# Adafruit_Qualia_S3_RGB666.net
KiCad netlist of a schematic drawn in EAGLE
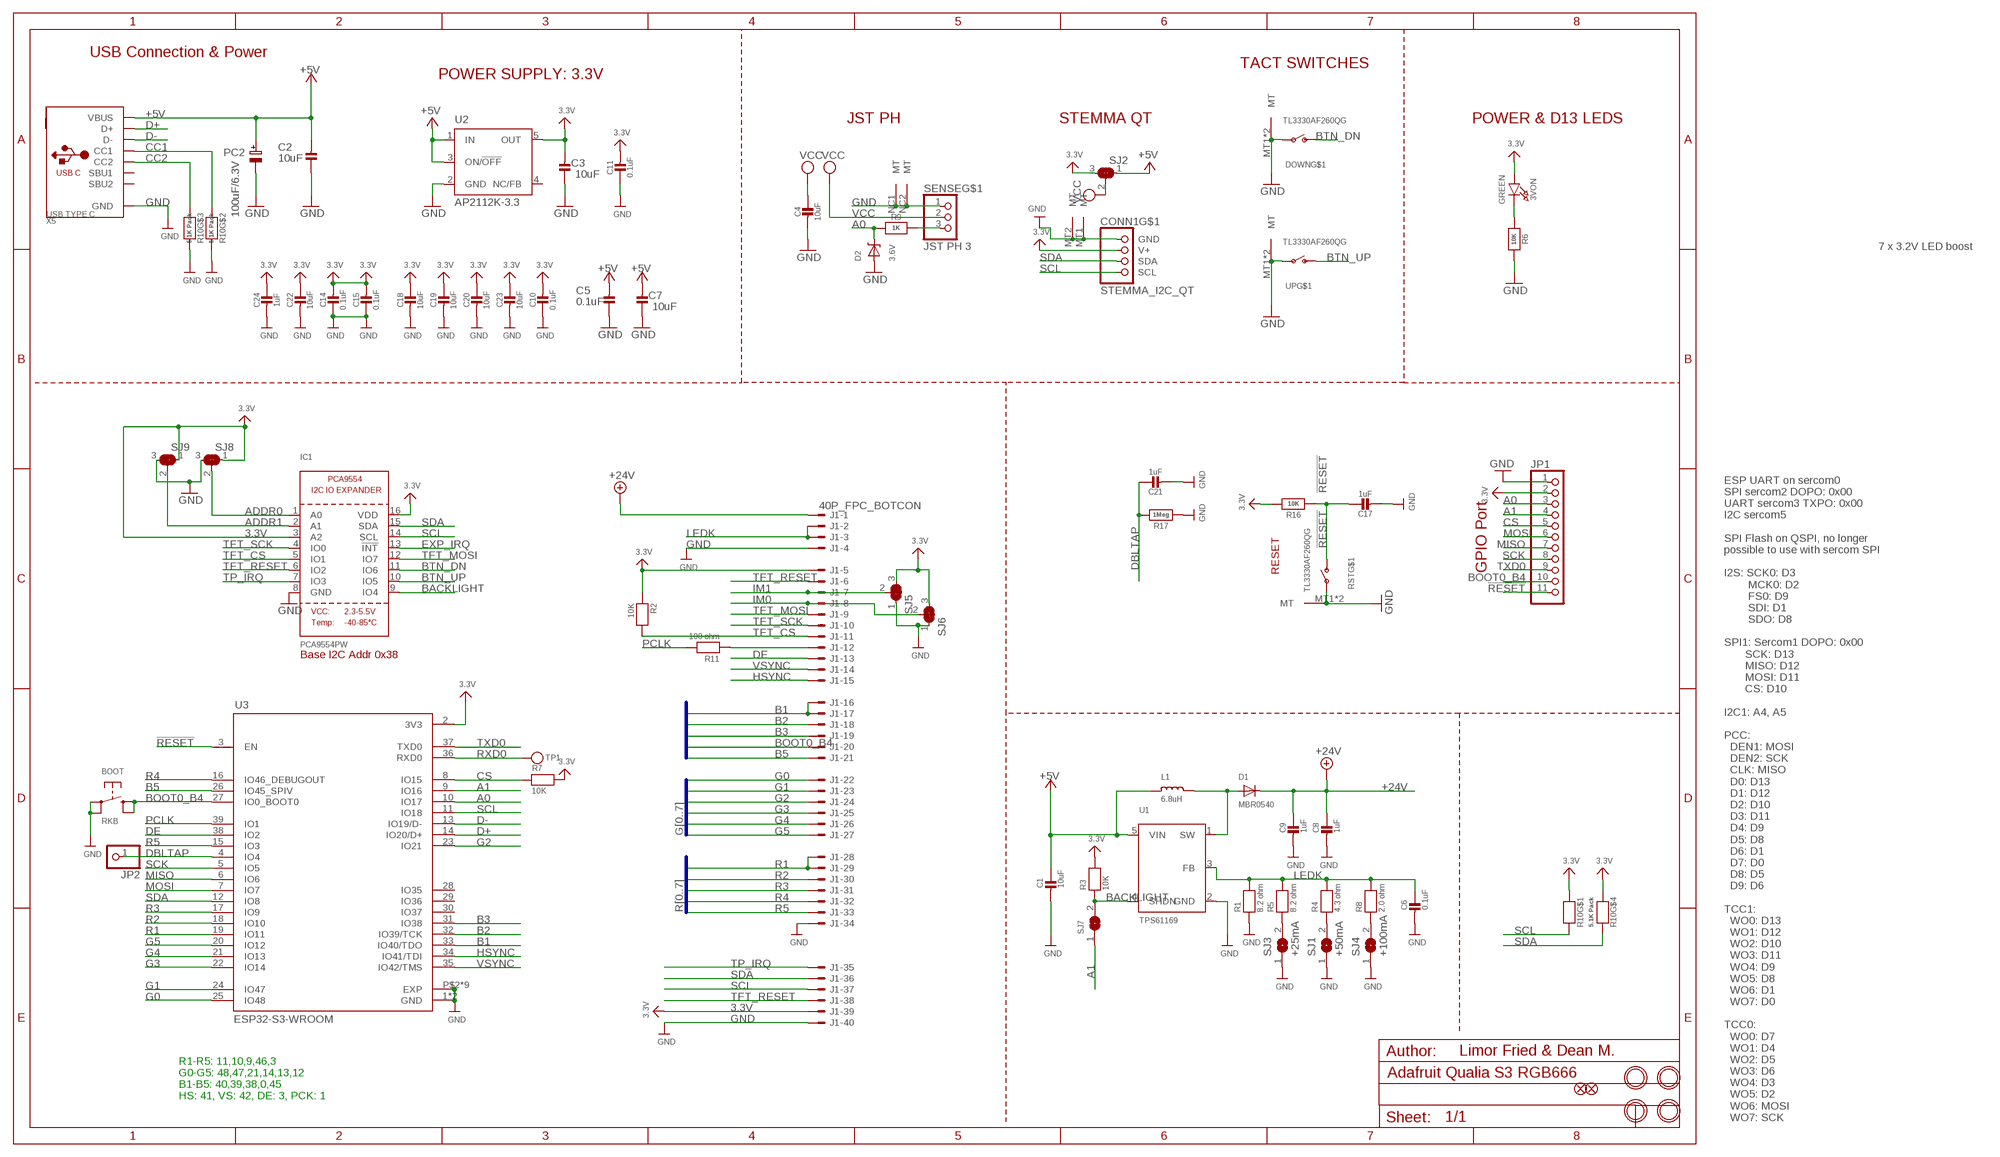
[diagram p0: schematic, sheet 1]

(export (version "E")
  (design (tool "Eeschema 10.0.6"))
  (components
    (comp (ref "3VON")
      (value "GREEN")
      (footprint "eagle-import:CHIPLED_0603_NOOUTLINE")
      (libsource (lib "eagle-import") (part "LED0603_NOOUTLINE"))
    )
    (comp (ref "BOOT")
      (value "RKB")
      (footprint "eagle-import:BTN_RKB2_4.6X2.8")
      (libsource (lib "eagle-import") (part "SWITCH_TACT_SMT_RKB2"))
    )
    (comp (ref "C1")
      (value "10uF")
      (footprint "eagle-import:0805-NO")
      (libsource (lib "eagle-import") (part "CAP_CERAMIC0805-NOOUTLINE"))
    )
    (comp (ref "C2")
      (value "10uF")
      (footprint "eagle-import:0805-NO")
      (libsource (lib "eagle-import") (part "CAP_CERAMIC0805-NOOUTLINE"))
    )
    (comp (ref "C3")
      (value "10uF")
      (footprint "eagle-import:0805-NO")
      (libsource (lib "eagle-import") (part "CAP_CERAMIC0805-NOOUTLINE"))
    )
    (comp (ref "C4")
      (value "10uF")
      (footprint "eagle-import:0805-NO")
      (libsource (lib "eagle-import") (part "CAP_CERAMIC0805-NOOUTLINE"))
    )
    (comp (ref "C5")
      (value "0.1uF")
      (footprint "eagle-import:0603-NO")
      (libsource (lib "eagle-import") (part "CAP_CERAMIC0603_NO"))
    )
    (comp (ref "C6")
      (value "0.1uF")
      (footprint "eagle-import:0603-NO")
      (libsource (lib "eagle-import") (part "CAP_CERAMIC0603_NO"))
    )
    (comp (ref "C7")
      (value "10uF")
      (footprint "eagle-import:0805-NO")
      (libsource (lib "eagle-import") (part "CAP_CERAMIC0805-NOOUTLINE"))
    )
    (comp (ref "C8")
      (value "1uF")
      (footprint "eagle-import:0603-NO")
      (libsource (lib "eagle-import") (part "CAP_CERAMIC0603_NO"))
    )
    (comp (ref "C9")
      (value "1uF")
      (footprint "eagle-import:0603-NO")
      (libsource (lib "eagle-import") (part "CAP_CERAMIC0603_NO"))
    )
    (comp (ref "C10")
      (value "0.1uF")
      (footprint "eagle-import:0603-NO")
      (libsource (lib "eagle-import") (part "CAP_CERAMIC0603_NO"))
    )
    (comp (ref "C11")
      (value "0.1uF")
      (footprint "eagle-import:0603-NO")
      (libsource (lib "eagle-import") (part "CAP_CERAMIC0603_NO"))
    )
    (comp (ref "C14")
      (value "0.1uF")
      (footprint "eagle-import:0603-NO")
      (libsource (lib "eagle-import") (part "CAP_CERAMIC0603_NO"))
    )
    (comp (ref "C15")
      (value "0.1uF")
      (footprint "eagle-import:0603-NO")
      (libsource (lib "eagle-import") (part "CAP_CERAMIC0603_NO"))
    )
    (comp (ref "C17")
      (value "1uF")
      (footprint "eagle-import:0603-NO")
      (libsource (lib "eagle-import") (part "CAP_CERAMIC0603_NO"))
    )
    (comp (ref "C18")
      (value "10uF")
      (footprint "eagle-import:0805-NO")
      (libsource (lib "eagle-import") (part "CAP_CERAMIC0805-NOOUTLINE"))
    )
    (comp (ref "C19")
      (value "10uF")
      (footprint "eagle-import:0805-NO")
      (libsource (lib "eagle-import") (part "CAP_CERAMIC0805-NOOUTLINE"))
    )
    (comp (ref "C20")
      (value "10uF")
      (footprint "eagle-import:0805-NO")
      (libsource (lib "eagle-import") (part "CAP_CERAMIC0805-NOOUTLINE"))
    )
    (comp (ref "C21")
      (value "1uF")
      (footprint "eagle-import:0603-NO")
      (libsource (lib "eagle-import") (part "CAP_CERAMIC0603_NO"))
    )
    (comp (ref "C22")
      (value "10uF")
      (footprint "eagle-import:0805-NO")
      (libsource (lib "eagle-import") (part "CAP_CERAMIC0805-NOOUTLINE"))
    )
    (comp (ref "C23")
      (value "10uF")
      (footprint "eagle-import:0805-NO")
      (libsource (lib "eagle-import") (part "CAP_CERAMIC0805-NOOUTLINE"))
    )
    (comp (ref "C24")
      (value "1uF")
      (footprint "eagle-import:0603-NO")
      (libsource (lib "eagle-import") (part "CAP_CERAMIC0603_NO"))
    )
    (comp (ref "CONN1")
      (value "STEMMA_I2C_QT")
      (footprint "eagle-import:JST_SH4")
      (libsource (lib "eagle-import") (part "STEMMA_I2C_QT"))
    )
    (comp (ref "D1")
      (value "MBR0540")
      (footprint "eagle-import:SOD-123")
      (libsource (lib "eagle-import") (part "DIODESOD-123"))
    )
    (comp (ref "D2")
      (value "3.6V")
      (footprint "eagle-import:SOD-323")
      (libsource (lib "eagle-import") (part "DIODE-ZENERSOD323"))
    )
    (comp (ref "DOWN")
      (value "TL3330AF260QG")
      (footprint "eagle-import:SPST_TACTILE_RA")
      (libsource (lib "eagle-import") (part "SWITCH_SPST_MNT_TACT_RA"))
    )
    (comp (ref "FID1")
      (value "FIDUCIAL_1MM")
      (footprint "eagle-import:FIDUCIAL_1MM")
      (libsource (lib "eagle-import") (part "FIDUCIAL_1MM"))
    )
    (comp (ref "FID2")
      (value "FIDUCIAL_1MM")
      (footprint "eagle-import:FIDUCIAL_1MM")
      (libsource (lib "eagle-import") (part "FIDUCIAL_1MM"))
    )
    (comp (ref "IC1")
      (value "PCA9554PW")
      (footprint "eagle-import:TSSOP16")
      (libsource (lib "eagle-import") (part "PCA9554PW"))
    )
    (comp (ref "J1")
      (value "40P_FPC_BOTCON")
      (footprint "eagle-import:FPC_40")
      (libsource (lib "eagle-import") (part "40PINFPC_GENERIC"))
    )
    (comp (ref "JP1")
      (value "HEADER-1X11")
      (footprint "eagle-import:1X11_ROUND")
      (libsource (lib "eagle-import") (part "HEADER-1X11"))
    )
    (comp (ref "JP2")
      (value "HEADER-1X1ROUND")
      (footprint "eagle-import:1X01_ROUND")
      (libsource (lib "eagle-import") (part "HEADER-1X1ROUND"))
    )
    (comp (ref "L1")
      (value "6.8uH")
      (footprint "eagle-import:INDUCTOR_5X5MM_NR5040_NOTHERMALS")
      (libsource (lib "eagle-import") (part "INDUCTORNR5040"))
    )
    (comp (ref "PC2")
      (value "100uF/6.3V")
      (footprint "eagle-import:PANASONIC_D")
      (libsource (lib "eagle-import") (part "CAP_ELECTROLYTICPANASONIC_D"))
    )
    (comp (ref "R1")
      (value "8.2 ohm")
      (footprint "eagle-import:0603-NO")
      (libsource (lib "eagle-import") (part "RESISTOR_0603_NOOUT"))
    )
    (comp (ref "R2")
      (value "10K")
      (footprint "eagle-import:0603-NO")
      (libsource (lib "eagle-import") (part "RESISTOR_0603_NOOUT"))
    )
    (comp (ref "R3")
      (value "10K")
      (footprint "eagle-import:0603-NO")
      (libsource (lib "eagle-import") (part "RESISTOR_0603_NOOUT"))
    )
    (comp (ref "R4")
      (value "4.3 ohm")
      (footprint "eagle-import:0603-NO")
      (libsource (lib "eagle-import") (part "RESISTOR_0603_NOOUT"))
    )
    (comp (ref "R5")
      (value "8.2 ohm")
      (footprint "eagle-import:0603-NO")
      (libsource (lib "eagle-import") (part "RESISTOR_0603_NOOUT"))
    )
    (comp (ref "R6")
      (value "10K")
      (footprint "eagle-import:0603-NO")
      (libsource (lib "eagle-import") (part "RESISTOR_0603_NOOUT"))
    )
    (comp (ref "R7")
      (value "10K")
      (footprint "eagle-import:0603-NO")
      (libsource (lib "eagle-import") (part "RESISTOR_0603_NOOUT"))
    )
    (comp (ref "R8")
      (value "2.0 ohm")
      (footprint "eagle-import:0603-NO")
      (libsource (lib "eagle-import") (part "RESISTOR_0603_NOOUT"))
    )
    (comp (ref "R9")
      (value "1K")
      (footprint "eagle-import:0603-NO")
      (libsource (lib "eagle-import") (part "RESISTOR_0603_NOOUT"))
    )
    (comp (ref "R10")
      (value "5.1K Pack")
      (footprint "eagle-import:RESPACK_4X0603")
      (libsource (lib "eagle-import") (part "RESISTOR_4PACK"))
    )
    (comp (ref "R11")
      (value "100 ohm")
      (footprint "eagle-import:0603-NO")
      (libsource (lib "eagle-import") (part "RESISTOR_0603_NOOUT"))
    )
    (comp (ref "R16")
      (value "10K")
      (footprint "eagle-import:0603-NO")
      (libsource (lib "eagle-import") (part "RESISTOR_0603_NOOUT"))
    )
    (comp (ref "R17")
      (value "1Meg")
      (footprint "eagle-import:0603-NO")
      (libsource (lib "eagle-import") (part "RESISTOR_0603_NOOUT"))
    )
    (comp (ref "RST")
      (value "TL3330AF260QG")
      (footprint "eagle-import:SPST_TACTILE_RA")
      (libsource (lib "eagle-import") (part "SWITCH_SPST_MNT_TACT_RA"))
    )
    (comp (ref "SENSE")
      (value "JST PH 3")
      (footprint "eagle-import:JSTPH3")
      (libsource (lib "eagle-import") (part "CON_JST_PH_3PIN"))
    )
    (comp (ref "SJ1")
      (value "+50mA")
      (footprint "eagle-import:SOLDERJUMPER_ARROW_NOPASTE")
      (libsource (lib "eagle-import") (part "SOLDERJUMPER"))
    )
    (comp (ref "SJ2")
      (value "SOLDERJUMPER_2WAY")
      (footprint "eagle-import:SOLDERJUMPER_2WAY_OPEN_NOPASTE")
      (libsource (lib "eagle-import") (part "SOLDERJUMPER_2WAY"))
    )
    (comp (ref "SJ3")
      (value "+25mA")
      (footprint "eagle-import:SOLDERJUMPER_ARROW_NOPASTE")
      (libsource (lib "eagle-import") (part "SOLDERJUMPER"))
    )
    (comp (ref "SJ4")
      (value "+100mA")
      (footprint "eagle-import:SOLDERJUMPER_ARROW_NOPASTE")
      (libsource (lib "eagle-import") (part "SOLDERJUMPER"))
    )
    (comp (ref "SJ5")
      (value "SOLDERJUMPER_2WAY")
      (footprint "eagle-import:SOLDERJUMPER_2WAY_OPEN_NOPASTE")
      (libsource (lib "eagle-import") (part "SOLDERJUMPER_2WAY"))
    )
    (comp (ref "SJ6")
      (value "SOLDERJUMPER_2WAY")
      (footprint "eagle-import:SOLDERJUMPER_2WAY_OPEN_NOPASTE")
      (libsource (lib "eagle-import") (part "SOLDERJUMPER_2WAY"))
    )
    (comp (ref "SJ7")
      (value "SOLDERJUMPER")
      (footprint "eagle-import:SOLDERJUMPER_ARROW_NOPASTE")
      (libsource (lib "eagle-import") (part "SOLDERJUMPER"))
    )
    (comp (ref "SJ8")
      (value "SOLDERJUMPER_2WAY")
      (footprint "eagle-import:SOLDERJUMPER_2WAY_OPEN_NOPASTE")
      (libsource (lib "eagle-import") (part "SOLDERJUMPER_2WAY"))
    )
    (comp (ref "SJ9")
      (value "SOLDERJUMPER_2WAY")
      (footprint "eagle-import:SOLDERJUMPER_2WAY_OPEN_NOPASTE")
      (libsource (lib "eagle-import") (part "SOLDERJUMPER_2WAY"))
    )
    (comp (ref "TP1")
      (value "TESTPOINTROUND1.5MMNO")
      (footprint "eagle-import:TESTPOINT_ROUND_1.5MM_NO")
      (libsource (lib "eagle-import") (part "TESTPOINTROUND1.5MMNO"))
    )
    (comp (ref "U$14")
      (value "MOUNTINGHOLE2.5")
      (footprint "eagle-import:MOUNTINGHOLE_2.5_PLATED")
      (libsource (lib "eagle-import") (part "MOUNTINGHOLE2.5"))
    )
    (comp (ref "U$19")
      (value "MOUNTINGHOLE2.5")
      (footprint "eagle-import:MOUNTINGHOLE_2.5_PLATED")
      (libsource (lib "eagle-import") (part "MOUNTINGHOLE2.5"))
    )
    (comp (ref "U$22")
      (value "MOUNTINGHOLE2.5")
      (footprint "eagle-import:MOUNTINGHOLE_2.5_PLATED")
      (libsource (lib "eagle-import") (part "MOUNTINGHOLE2.5"))
    )
    (comp (ref "U$24")
      (value "MOUNTINGHOLE2.5")
      (footprint "eagle-import:MOUNTINGHOLE_2.5_PLATED")
      (libsource (lib "eagle-import") (part "MOUNTINGHOLE2.5"))
    )
    (comp (ref "U1")
      (value "TPS61169")
      (footprint "eagle-import:SC70-5")
      (libsource (lib "eagle-import") (part "VREG_BOOST_5PIN_SC70"))
    )
    (comp (ref "U2")
      (value "AP2112K-3.3")
      (footprint "eagle-import:SOT23-DBV")
      (libsource (lib "eagle-import") (part "LP2985-XXDBVR33"))
    )
    (comp (ref "U3")
      (value "ESP32-S3-WROOM")
      (footprint "eagle-import:S3-WROOM32")
      (libsource (lib "eagle-import") (part "ESP32-S3-WROOM"))
    )
    (comp (ref "UP")
      (value "TL3330AF260QG")
      (footprint "eagle-import:SPST_TACTILE_RA")
      (libsource (lib "eagle-import") (part "SWITCH_SPST_MNT_TACT_RA"))
    )
    (comp (ref "X5")
      (value "USB TYPE C")
      (footprint "eagle-import:USB_C_CUSB31-CFM2AX-01-X")
      (libsource (lib "eagle-import") (part "USB_C"))
    )
  )
  (nets
    (net (code "6") (name "+5V") (class "Default")
      (node (ref "C1") (pin "1") (pinfunction "1_1") (pintype "passive"))
      (node (ref "C2") (pin "2") (pinfunction "2_2") (pintype "passive"))
      (node (ref "C5") (pin "2") (pinfunction "2_2") (pintype "passive"))
      (node (ref "C7") (pin "2") (pinfunction "2_2") (pintype "passive"))
      (node (ref "L1") (pin "P$1") (pinfunction "1_P$1") (pintype "passive"))
      (node (ref "PC2") (pin "+") (pinfunction "+_+") (pintype "passive"))
      (node (ref "SJ2") (pin "1") (pinfunction "1_1") (pintype "passive"))
      (node (ref "U1") (pin "5") (pinfunction "VIN_5") (pintype "bidirectional"))
      (node (ref "U2") (pin "1") (pinfunction "IN_1") (pintype "input"))
      (node (ref "U2") (pin "3") (pinfunction "ON/~{OFF}_3") (pintype "input"))
      (node (ref "X5") (pin "A4B9") (pinfunction "VBUS_A4B9") (pintype "power_in"))
      (node (ref "X5") (pin "B4A9") (pinfunction "VBUS_B4A9") (pintype "power_in"))
    )
    (net (code "7") (name "+24V") (class "Default")
      (node (ref "C8") (pin "1") (pinfunction "1_1") (pintype "passive"))
      (node (ref "C9") (pin "1") (pinfunction "1_1") (pintype "passive"))
      (node (ref "D1") (pin "C") (pinfunction "C_C") (pintype "passive"))
      (node (ref "J1") (pin "1") (pinfunction "MSV_1") (pintype "passive"))
    )
    (net (code "8") (name "/A0") (class "Default")
      (node (ref "D2") (pin "C") (pinfunction "C_C") (pintype "passive"))
      (node (ref "JP1") (pin "3") (pinfunction "3_3") (pintype "passive"))
      (node (ref "R9") (pin "2") (pinfunction "2_2") (pintype "passive"))
      (node (ref "U3") (pin "10") (pinfunction "IO17_10") (pintype "bidirectional"))
    )
    (net (code "9") (name "/A1") (class "Default")
      (node (ref "JP1") (pin "4") (pinfunction "4_4") (pintype "passive"))
      (node (ref "SJ7") (pin "1") (pinfunction "1_1") (pintype "passive"))
      (node (ref "U3") (pin "9") (pinfunction "IO16_9") (pintype "bidirectional"))
    )
    (net (code "10") (name "/ADDR0") (class "Default")
      (node (ref "IC1") (pin "1") (pinfunction "A0_1") (pintype "input"))
      (node (ref "SJ8") (pin "2") (pinfunction "2_2") (pintype "passive"))
    )
    (net (code "11") (name "/ADDR1") (class "Default")
      (node (ref "IC1") (pin "2") (pinfunction "A1_2") (pintype "input"))
      (node (ref "SJ9") (pin "2") (pinfunction "2_2") (pintype "passive"))
    )
    (net (code "12") (name "/B1") (class "Default")
      (node (ref "J1") (pin "16") (pinfunction "MS_16") (pintype "passive"))
      (node (ref "J1") (pin "17") (pinfunction "MS_17") (pintype "passive"))
      (node (ref "U3") (pin "33") (pinfunction "IO40/TDO_33") (pintype "bidirectional"))
    )
    (net (code "13") (name "/B2") (class "Default")
      (node (ref "J1") (pin "18") (pinfunction "MS_18") (pintype "passive"))
      (node (ref "U3") (pin "32") (pinfunction "IO39/TCK_32") (pintype "bidirectional"))
    )
    (net (code "14") (name "/B3") (class "Default")
      (node (ref "J1") (pin "19") (pinfunction "MS_19") (pintype "passive"))
      (node (ref "U3") (pin "31") (pinfunction "IO38_31") (pintype "bidirectional"))
    )
    (net (code "15") (name "/B5") (class "Default")
      (node (ref "J1") (pin "21") (pinfunction "MS_21") (pintype "passive"))
      (node (ref "U3") (pin "26") (pinfunction "IO45_SPIV_26") (pintype "bidirectional"))
    )
    (net (code "16") (name "/BACKLIGHT") (class "Default")
      (node (ref "IC1") (pin "9") (pinfunction "IO4_9") (pintype "bidirectional"))
      (node (ref "R3") (pin "1") (pinfunction "1_1") (pintype "passive"))
      (node (ref "SJ7") (pin "2") (pinfunction "2_2") (pintype "passive"))
      (node (ref "U1") (pin "4") (pinfunction "SHDN_4") (pintype "bidirectional"))
    )
    (net (code "17") (name "/BOOT0_B4") (class "Default")
      (node (ref "BOOT") (pin "B") (pinfunction "S_B") (pintype "passive"))
      (node (ref "BOOT") (pin "B'") (pinfunction "S1_B'") (pintype "passive"))
      (node (ref "J1") (pin "20") (pinfunction "MS_20") (pintype "passive"))
      (node (ref "JP1") (pin "10") (pinfunction "10_10") (pintype "passive"))
      (node (ref "U3") (pin "27") (pinfunction "IO0_BOOT0_27") (pintype "bidirectional"))
    )
    (net (code "18") (name "/BTN_DN") (class "Default")
      (node (ref "DOWN") (pin "2") (pinfunction "S_2") (pintype "passive"))
      (node (ref "IC1") (pin "11") (pinfunction "IO6_11") (pintype "bidirectional"))
    )
    (net (code "19") (name "/BTN_UP") (class "Default")
      (node (ref "IC1") (pin "10") (pinfunction "IO5_10") (pintype "bidirectional"))
      (node (ref "UP") (pin "2") (pinfunction "S_2") (pintype "passive"))
    )
    (net (code "20") (name "/CC1") (class "Default")
      (node (ref "R10") (pin "2") (pinfunction "1_2") (pintype "passive"))
      (node (ref "X5") (pin "A5") (pinfunction "CC1_A5") (pintype "bidirectional"))
    )
    (net (code "21") (name "/CC2") (class "Default")
      (node (ref "R10") (pin "3") (pinfunction "1_3") (pintype "passive"))
      (node (ref "X5") (pin "B5") (pinfunction "CC2_B5") (pintype "bidirectional"))
    )
    (net (code "22") (name "/CS") (class "Default")
      (node (ref "JP1") (pin "5") (pinfunction "5_5") (pintype "passive"))
      (node (ref "R7") (pin "1") (pinfunction "1_1") (pintype "passive"))
      (node (ref "U3") (pin "8") (pinfunction "IO15_8") (pintype "bidirectional"))
    )
    (net (code "23") (name "/D+") (class "Default")
      (node (ref "U3") (pin "14") (pinfunction "IO20/D+_14") (pintype "bidirectional"))
      (node (ref "X5") (pin "A6") (pinfunction "D+_A6") (pintype "bidirectional"))
      (node (ref "X5") (pin "B6") (pinfunction "D+_B6") (pintype "bidirectional"))
    )
    (net (code "24") (name "/D-") (class "Default")
      (node (ref "U3") (pin "13") (pinfunction "IO19/D-_13") (pintype "bidirectional"))
      (node (ref "X5") (pin "A7") (pinfunction "D-_A7") (pintype "bidirectional"))
      (node (ref "X5") (pin "B7") (pinfunction "D-_B7") (pintype "bidirectional"))
    )
    (net (code "25") (name "/DBLTAP") (class "Default")
      (node (ref "C21") (pin "1") (pinfunction "1_1") (pintype "passive"))
      (node (ref "JP2") (pin "1") (pinfunction "1_1") (pintype "passive"))
      (node (ref "R17") (pin "2") (pinfunction "2_2") (pintype "passive"))
      (node (ref "U3") (pin "4") (pinfunction "IO4_4") (pintype "bidirectional"))
    )
    (net (code "26") (name "/DE") (class "Default")
      (node (ref "J1") (pin "13") (pinfunction "MS_13") (pintype "passive"))
      (node (ref "U3") (pin "38") (pinfunction "IO2_38") (pintype "bidirectional"))
    )
    (net (code "27") (name "/EXP_IRQ") (class "Default")
      (node (ref "IC1") (pin "13") (pinfunction "~{INT}_13") (pintype "output"))
    )
    (net (code "28") (name "/G0") (class "Default")
      (node (ref "J1") (pin "22") (pinfunction "MS_22") (pintype "passive"))
      (node (ref "U3") (pin "25") (pinfunction "IO48_25") (pintype "input"))
    )
    (net (code "29") (name "/G1") (class "Default")
      (node (ref "J1") (pin "23") (pinfunction "MS_23") (pintype "passive"))
      (node (ref "U3") (pin "24") (pinfunction "IO47_24") (pintype "bidirectional"))
    )
    (net (code "30") (name "/G2") (class "Default")
      (node (ref "J1") (pin "24") (pinfunction "MS_24") (pintype "passive"))
      (node (ref "U3") (pin "23") (pinfunction "IO21_23") (pintype "bidirectional"))
    )
    (net (code "31") (name "/G3") (class "Default")
      (node (ref "J1") (pin "25") (pinfunction "MS_25") (pintype "passive"))
      (node (ref "U3") (pin "22") (pinfunction "IO14_22") (pintype "bidirectional"))
    )
    (net (code "32") (name "/G4") (class "Default")
      (node (ref "J1") (pin "26") (pinfunction "MS_26") (pintype "passive"))
      (node (ref "U3") (pin "21") (pinfunction "IO13_21") (pintype "bidirectional"))
    )
    (net (code "33") (name "/G5") (class "Default")
      (node (ref "J1") (pin "27") (pinfunction "MS_27") (pintype "passive"))
      (node (ref "U3") (pin "20") (pinfunction "IO12_20") (pintype "bidirectional"))
    )
    (net (code "35") (name "/HSYNC") (class "Default")
      (node (ref "J1") (pin "15") (pinfunction "MS_15") (pintype "passive"))
      (node (ref "U3") (pin "34") (pinfunction "IO41/TDI_34") (pintype "bidirectional"))
    )
    (net (code "36") (name "/IM0") (class "Default")
      (node (ref "J1") (pin "8") (pinfunction "MS_8") (pintype "passive"))
      (node (ref "SJ6") (pin "2") (pinfunction "2_2") (pintype "passive"))
    )
    (net (code "37") (name "/IM1") (class "Default")
      (node (ref "J1") (pin "7") (pinfunction "MS_7") (pintype "passive"))
      (node (ref "SJ5") (pin "2") (pinfunction "2_2") (pintype "passive"))
    )
    (net (code "38") (name "/LEDK") (class "Default")
      (node (ref "C6") (pin "1") (pinfunction "1_1") (pintype "passive"))
      (node (ref "J1") (pin "2") (pinfunction "MS_2") (pintype "passive"))
      (node (ref "J1") (pin "3") (pinfunction "MS_3") (pintype "passive"))
      (node (ref "R1") (pin "2") (pinfunction "2_2") (pintype "passive"))
      (node (ref "R4") (pin "2") (pinfunction "2_2") (pintype "passive"))
      (node (ref "R5") (pin "2") (pinfunction "2_2") (pintype "passive"))
      (node (ref "R8") (pin "2") (pinfunction "2_2") (pintype "passive"))
      (node (ref "U1") (pin "3") (pinfunction "FB_3") (pintype "bidirectional"))
    )
    (net (code "39") (name "/MISO") (class "Default")
      (node (ref "JP1") (pin "7") (pinfunction "7_7") (pintype "passive"))
      (node (ref "U3") (pin "6") (pinfunction "IO6_6") (pintype "bidirectional"))
    )
    (net (code "40") (name "/MOSI") (class "Default")
      (node (ref "JP1") (pin "6") (pinfunction "6_6") (pintype "passive"))
      (node (ref "U3") (pin "7") (pinfunction "IO7_7") (pintype "bidirectional"))
    )
    (net (code "41") (name "/PCLK") (class "Default")
      (node (ref "R11") (pin "2") (pinfunction "2_2") (pintype "passive"))
      (node (ref "U3") (pin "39") (pinfunction "IO1_39") (pintype "bidirectional"))
    )
    (net (code "42") (name "/R1") (class "Default")
      (node (ref "J1") (pin "28") (pinfunction "MS_28") (pintype "passive"))
      (node (ref "J1") (pin "29") (pinfunction "MS_29") (pintype "passive"))
      (node (ref "U3") (pin "19") (pinfunction "IO11_19") (pintype "bidirectional"))
    )
    (net (code "43") (name "/R2") (class "Default")
      (node (ref "J1") (pin "30") (pinfunction "MS_30") (pintype "passive"))
      (node (ref "U3") (pin "18") (pinfunction "IO10_18") (pintype "bidirectional"))
    )
    (net (code "44") (name "/R3") (class "Default")
      (node (ref "J1") (pin "31") (pinfunction "MS_31") (pintype "passive"))
      (node (ref "U3") (pin "17") (pinfunction "IO9_17") (pintype "bidirectional"))
    )
    (net (code "45") (name "/R4") (class "Default")
      (node (ref "J1") (pin "32") (pinfunction "MS_32") (pintype "passive"))
      (node (ref "U3") (pin "16") (pinfunction "IO46_DEBUGOUT_16") (pintype "input"))
    )
    (net (code "46") (name "/R5") (class "Default")
      (node (ref "J1") (pin "33") (pinfunction "MS_33") (pintype "passive"))
      (node (ref "U3") (pin "15") (pinfunction "IO3_15") (pintype "bidirectional"))
    )
    (net (code "47") (name "/RXD0") (class "Default")
      (node (ref "TP1") (pin "P$1") (pinfunction "P$1_P$1") (pintype "bidirectional"))
      (node (ref "U3") (pin "36") (pinfunction "RXD0_36") (pintype "bidirectional"))
    )
    (net (code "49") (name "/SCK") (class "Default")
      (node (ref "JP1") (pin "8") (pinfunction "8_8") (pintype "passive"))
      (node (ref "U3") (pin "5") (pinfunction "IO5_5") (pintype "bidirectional"))
    )
    (net (code "50") (name "/SCL") (class "Default")
      (node (ref "CONN1") (pin "4") (pinfunction "SCL_4") (pintype "passive"))
      (node (ref "IC1") (pin "14") (pinfunction "SCL_14") (pintype "bidirectional"))
      (node (ref "J1") (pin "37") (pinfunction "MS_37") (pintype "passive"))
      (node (ref "R10") (pin "8") (pinfunction "2_8") (pintype "passive"))
      (node (ref "U3") (pin "11") (pinfunction "IO18_11") (pintype "bidirectional"))
    )
    (net (code "51") (name "/SDA") (class "Default")
      (node (ref "CONN1") (pin "3") (pinfunction "SDA_3") (pintype "passive"))
      (node (ref "IC1") (pin "15") (pinfunction "SDA_15") (pintype "bidirectional"))
      (node (ref "J1") (pin "36") (pinfunction "MS_36") (pintype "passive"))
      (node (ref "R10") (pin "5") (pinfunction "2_5") (pintype "passive"))
      (node (ref "U3") (pin "12") (pinfunction "IO8_12") (pintype "bidirectional"))
    )
    (net (code "52") (name "/TFT_CS") (class "Default")
      (node (ref "IC1") (pin "5") (pinfunction "IO1_5") (pintype "bidirectional"))
      (node (ref "J1") (pin "11") (pinfunction "MS_11") (pintype "passive"))
      (node (ref "R2") (pin "2") (pinfunction "2_2") (pintype "passive"))
    )
    (net (code "53") (name "/TFT_MOSI") (class "Default")
      (node (ref "IC1") (pin "12") (pinfunction "IO7_12") (pintype "bidirectional"))
      (node (ref "J1") (pin "9") (pinfunction "MS_9") (pintype "passive"))
    )
    (net (code "54") (name "/TFT_RESET") (class "Default")
      (node (ref "IC1") (pin "6") (pinfunction "IO2_6") (pintype "bidirectional"))
      (node (ref "J1") (pin "38") (pinfunction "MS_38") (pintype "passive"))
      (node (ref "J1") (pin "6") (pinfunction "MS_6") (pintype "passive"))
    )
    (net (code "55") (name "/TFT_SCK") (class "Default")
      (node (ref "IC1") (pin "4") (pinfunction "IO0_4") (pintype "bidirectional"))
      (node (ref "J1") (pin "10") (pinfunction "MS_10") (pintype "passive"))
    )
    (net (code "56") (name "/TP_IRQ") (class "Default")
      (node (ref "IC1") (pin "7") (pinfunction "IO3_7") (pintype "bidirectional"))
      (node (ref "J1") (pin "35") (pinfunction "MS_35") (pintype "passive"))
    )
    (net (code "57") (name "/TXD0") (class "Default")
      (node (ref "JP1") (pin "9") (pinfunction "9_9") (pintype "passive"))
      (node (ref "U3") (pin "37") (pinfunction "TXD0_37") (pintype "bidirectional"))
    )
    (net (code "58") (name "/VSYNC") (class "Default")
      (node (ref "J1") (pin "14") (pinfunction "MS_14") (pintype "passive"))
      (node (ref "U3") (pin "35") (pinfunction "IO42/TMS_35") (pintype "bidirectional"))
    )
    (net (code "59") (name "/~{RESET}") (class "Default")
      (node (ref "C17") (pin "1") (pinfunction "1_1") (pintype "passive"))
      (node (ref "JP1") (pin "11") (pinfunction "11_11") (pintype "passive"))
      (node (ref "R16") (pin "1") (pinfunction "1_1") (pintype "passive"))
      (node (ref "RST") (pin "2") (pinfunction "S_2") (pintype "passive"))
      (node (ref "U3") (pin "3") (pinfunction "EN_3") (pintype "input"))
    )
    (net (code "60") (name "3.3V") (class "Default")
      (node (ref "3VON") (pin "A") (pinfunction "A_A") (pintype "passive"))
      (node (ref "C10") (pin "2") (pinfunction "2_2") (pintype "passive"))
      (node (ref "C11") (pin "2") (pinfunction "2_2") (pintype "passive"))
      (node (ref "C14") (pin "2") (pinfunction "2_2") (pintype "passive"))
      (node (ref "C15") (pin "2") (pinfunction "2_2") (pintype "passive"))
      (node (ref "C18") (pin "1") (pinfunction "1_1") (pintype "passive"))
      (node (ref "C19") (pin "1") (pinfunction "1_1") (pintype "passive"))
      (node (ref "C20") (pin "1") (pinfunction "1_1") (pintype "passive"))
      (node (ref "C22") (pin "1") (pinfunction "1_1") (pintype "passive"))
      (node (ref "C23") (pin "1") (pinfunction "1_1") (pintype "passive"))
      (node (ref "C24") (pin "1") (pinfunction "1_1") (pintype "passive"))
      (node (ref "C3") (pin "2") (pinfunction "2_2") (pintype "passive"))
      (node (ref "CONN1") (pin "2") (pinfunction "V+_2") (pintype "passive"))
      (node (ref "IC1") (pin "16") (pinfunction "VDD_16") (pintype "power_in"))
      (node (ref "IC1") (pin "3") (pinfunction "A2_3") (pintype "input"))
      (node (ref "J1") (pin "39") (pinfunction "MS_39") (pintype "passive"))
      (node (ref "J1") (pin "5") (pinfunction "MS_5") (pintype "passive"))
      (node (ref "JP1") (pin "2") (pinfunction "2_2") (pintype "passive"))
      (node (ref "R10") (pin "1") (pinfunction "1_1") (pintype "passive"))
      (node (ref "R10") (pin "4") (pinfunction "1_4") (pintype "passive"))
      (node (ref "R16") (pin "2") (pinfunction "2_2") (pintype "passive"))
      (node (ref "R2") (pin "1") (pinfunction "1_1") (pintype "passive"))
      (node (ref "R3") (pin "2") (pinfunction "2_2") (pintype "passive"))
      (node (ref "R7") (pin "2") (pinfunction "2_2") (pintype "passive"))
      (node (ref "SJ2") (pin "3") (pinfunction "3_3") (pintype "passive"))
      (node (ref "SJ5") (pin "3") (pinfunction "3_3") (pintype "passive"))
      (node (ref "SJ6") (pin "3") (pinfunction "3_3") (pintype "passive"))
      (node (ref "SJ8") (pin "1") (pinfunction "1_1") (pintype "passive"))
      (node (ref "SJ9") (pin "1") (pinfunction "1_1") (pintype "passive"))
      (node (ref "U2") (pin "5") (pinfunction "OUT_5") (pintype "passive"))
      (node (ref "U3") (pin "2") (pinfunction "3V3_2") (pintype "power_in"))
    )
    (net (code "61") (name "GND") (class "Default")
      (node (ref "BOOT") (pin "A") (pinfunction "P_A") (pintype "passive"))
      (node (ref "BOOT") (pin "A'") (pinfunction "P1_A'") (pintype "passive"))
      (node (ref "C1") (pin "2") (pinfunction "2_2") (pintype "passive"))
      (node (ref "C10") (pin "1") (pinfunction "1_1") (pintype "passive"))
      (node (ref "C11") (pin "1") (pinfunction "1_1") (pintype "passive"))
      (node (ref "C14") (pin "1") (pinfunction "1_1") (pintype "passive"))
      (node (ref "C15") (pin "1") (pinfunction "1_1") (pintype "passive"))
      (node (ref "C17") (pin "2") (pinfunction "2_2") (pintype "passive"))
      (node (ref "C18") (pin "2") (pinfunction "2_2") (pintype "passive"))
      (node (ref "C19") (pin "2") (pinfunction "2_2") (pintype "passive"))
      (node (ref "C2") (pin "1") (pinfunction "1_1") (pintype "passive"))
      (node (ref "C20") (pin "2") (pinfunction "2_2") (pintype "passive"))
      (node (ref "C21") (pin "2") (pinfunction "2_2") (pintype "passive"))
      (node (ref "C22") (pin "2") (pinfunction "2_2") (pintype "passive"))
      (node (ref "C23") (pin "2") (pinfunction "2_2") (pintype "passive"))
      (node (ref "C24") (pin "2") (pinfunction "2_2") (pintype "passive"))
      (node (ref "C3") (pin "1") (pinfunction "1_1") (pintype "passive"))
      (node (ref "C4") (pin "2") (pinfunction "2_2") (pintype "passive"))
      (node (ref "C5") (pin "1") (pinfunction "1_1") (pintype "passive"))
      (node (ref "C6") (pin "2") (pinfunction "2_2") (pintype "passive"))
      (node (ref "C7") (pin "1") (pinfunction "1_1") (pintype "passive"))
      (node (ref "C8") (pin "2") (pinfunction "2_2") (pintype "passive"))
      (node (ref "C9") (pin "2") (pinfunction "2_2") (pintype "passive"))
      (node (ref "CONN1") (pin "1") (pinfunction "GND_1") (pintype "passive"))
      (node (ref "CONN1") (pin "MT1") (pinfunction "MT_MT1") (pintype "bidirectional"))
      (node (ref "CONN1") (pin "MT2") (pinfunction "MT_MT2") (pintype "bidirectional"))
      (node (ref "D2") (pin "A") (pinfunction "A_A") (pintype "passive"))
      (node (ref "DOWN") (pin "1") (pinfunction "P_1") (pintype "passive"))
      (node (ref "DOWN") (pin "MT1") (pinfunction "MT_MT1") (pintype "bidirectional"))
      (node (ref "DOWN") (pin "MT2") (pinfunction "MT_MT2") (pintype "bidirectional"))
      (node (ref "IC1") (pin "8") (pinfunction "GND_8") (pintype "power_in"))
      (node (ref "J1") (pin "34") (pinfunction "MS_34") (pintype "passive"))
      (node (ref "J1") (pin "4") (pinfunction "MS_4") (pintype "passive"))
      (node (ref "J1") (pin "40") (pinfunction "MS_40") (pintype "passive"))
      (node (ref "JP1") (pin "1") (pinfunction "1_1") (pintype "passive"))
      (node (ref "PC2") (pin "-") (pinfunction "-_-") (pintype "passive"))
      (node (ref "R1") (pin "1") (pinfunction "1_1") (pintype "passive"))
      (node (ref "R10") (pin "6") (pinfunction "2_6") (pintype "passive"))
      (node (ref "R10") (pin "7") (pinfunction "2_7") (pintype "passive"))
      (node (ref "R17") (pin "1") (pinfunction "1_1") (pintype "passive"))
      (node (ref "R6") (pin "2") (pinfunction "2_2") (pintype "passive"))
      (node (ref "RST") (pin "1") (pinfunction "P_1") (pintype "passive"))
      (node (ref "RST") (pin "MT1") (pinfunction "MT_MT1") (pintype "bidirectional"))
      (node (ref "RST") (pin "MT2") (pinfunction "MT_MT2") (pintype "bidirectional"))
      (node (ref "SENSE") (pin "1") (pinfunction "1_1") (pintype "passive"))
      (node (ref "SENSE") (pin "NC1") (pinfunction "MT_NC1") (pintype "bidirectional"))
      (node (ref "SENSE") (pin "NC2") (pinfunction "MT_NC2") (pintype "bidirectional"))
      (node (ref "SJ1") (pin "1") (pinfunction "1_1") (pintype "passive"))
      (node (ref "SJ3") (pin "1") (pinfunction "1_1") (pintype "passive"))
      (node (ref "SJ4") (pin "1") (pinfunction "1_1") (pintype "passive"))
      (node (ref "SJ5") (pin "1") (pinfunction "1_1") (pintype "passive"))
      (node (ref "SJ6") (pin "1") (pinfunction "1_1") (pintype "passive"))
      (node (ref "SJ8") (pin "3") (pinfunction "3_3") (pintype "passive"))
      (node (ref "SJ9") (pin "3") (pinfunction "3_3") (pintype "passive"))
      (node (ref "U1") (pin "2") (pinfunction "GND_2") (pintype "bidirectional"))
      (node (ref "U2") (pin "2") (pinfunction "GND_2") (pintype "power_in"))
      (node (ref "U3") (pin "1") (pinfunction "GND_1") (pintype "power_in"))
      (node (ref "U3") (pin "40") (pinfunction "GND_40") (pintype "power_in"))
      (node (ref "U3") (pin "P$10") (pinfunction "EXP_P$10") (pintype "power_in"))
      (node (ref "U3") (pin "P$2") (pinfunction "EXP_P$2") (pintype "power_in"))
      (node (ref "U3") (pin "P$3") (pinfunction "EXP_P$3") (pintype "power_in"))
      (node (ref "U3") (pin "P$4") (pinfunction "EXP_P$4") (pintype "power_in"))
      (node (ref "U3") (pin "P$5") (pinfunction "EXP_P$5") (pintype "power_in"))
      (node (ref "U3") (pin "P$6") (pinfunction "EXP_P$6") (pintype "power_in"))
      (node (ref "U3") (pin "P$7") (pinfunction "EXP_P$7") (pintype "power_in"))
      (node (ref "U3") (pin "P$8") (pinfunction "EXP_P$8") (pintype "power_in"))
      (node (ref "U3") (pin "P$9") (pinfunction "EXP_P$9") (pintype "power_in"))
      (node (ref "UP") (pin "1") (pinfunction "P_1") (pintype "passive"))
      (node (ref "UP") (pin "MT1") (pinfunction "MT_MT1") (pintype "bidirectional"))
      (node (ref "UP") (pin "MT2") (pinfunction "MT_MT2") (pintype "bidirectional"))
      (node (ref "X5") (pin "A1B12") (pinfunction "GND_A1B12") (pintype "power_in"))
      (node (ref "X5") (pin "B1A12") (pinfunction "GND_B1A12") (pintype "power_in"))
    )
    (net (code "62") (name "Net-(3VON-PadC)") (class "Default")
      (node (ref "3VON") (pin "C") (pinfunction "C_C") (pintype "passive"))
      (node (ref "R6") (pin "1") (pinfunction "1_1") (pintype "passive"))
    )
    (net (code "63") (name "Net-(J1D-MS)") (class "Default")
      (node (ref "J1") (pin "12") (pinfunction "MS_12") (pintype "passive"))
      (node (ref "R11") (pin "1") (pinfunction "1_1") (pintype "passive"))
    )
    (net (code "64") (name "Net-(L1-2)") (class "Default")
      (node (ref "D1") (pin "A") (pinfunction "A_A") (pintype "passive"))
      (node (ref "L1") (pin "P$2") (pinfunction "2_P$2") (pintype "passive"))
      (node (ref "U1") (pin "1") (pinfunction "SW_1") (pintype "bidirectional"))
    )
    (net (code "65") (name "Net-(R4-Pad1)") (class "Default")
      (node (ref "R4") (pin "1") (pinfunction "1_1") (pintype "passive"))
      (node (ref "SJ1") (pin "2") (pinfunction "2_2") (pintype "passive"))
    )
    (net (code "66") (name "Net-(R5-Pad1)") (class "Default")
      (node (ref "R5") (pin "1") (pinfunction "1_1") (pintype "passive"))
      (node (ref "SJ3") (pin "2") (pinfunction "2_2") (pintype "passive"))
    )
    (net (code "67") (name "Net-(R8-Pad1)") (class "Default")
      (node (ref "R8") (pin "1") (pinfunction "1_1") (pintype "passive"))
      (node (ref "SJ4") (pin "2") (pinfunction "2_2") (pintype "passive"))
    )
    (net (code "68") (name "Net-(R9-Pad1)") (class "Default")
      (node (ref "R9") (pin "1") (pinfunction "1_1") (pintype "passive"))
      (node (ref "SENSE") (pin "3") (pinfunction "3_3") (pintype "passive"))
    )
    (net (code "69") (name "VCC") (class "Default")
      (node (ref "C4") (pin "1") (pinfunction "1_1") (pintype "passive"))
      (node (ref "SENSE") (pin "2") (pinfunction "2_2") (pintype "passive"))
      (node (ref "SJ2") (pin "2") (pinfunction "2_2") (pintype "passive"))
    )
    (net (code "70") (name "unconnected-(U2-NC{slash}FB-Pad4)") (class "Default")
      (node (ref "U2") (pin "4") (pinfunction "NC/FB_4") (pintype "passive"))
    )
    (net (code "71") (name "unconnected-(U3-IO35-Pad28)") (class "Default")
      (node (ref "U3") (pin "28") (pinfunction "IO35_28") (pintype "input"))
    )
    (net (code "72") (name "unconnected-(U3-IO36-Pad29)") (class "Default")
      (node (ref "U3") (pin "29") (pinfunction "IO36_29") (pintype "bidirectional"))
    )
    (net (code "73") (name "unconnected-(U3-IO37-Pad30)") (class "Default")
      (node (ref "U3") (pin "30") (pinfunction "IO37_30") (pintype "bidirectional"))
    )
    (net (code "74") (name "unconnected-(X5-SBU1-PadA8)") (class "Default")
      (node (ref "X5") (pin "A8") (pinfunction "SBU1_A8") (pintype "bidirectional"))
    )
    (net (code "75") (name "unconnected-(X5-SBU2-PadB8)") (class "Default")
      (node (ref "X5") (pin "B8") (pinfunction "SBU2_B8") (pintype "bidirectional"))
    )
  )
)
